# Intervalometer.net
KiCad netlist of a schematic drawn in EAGLE
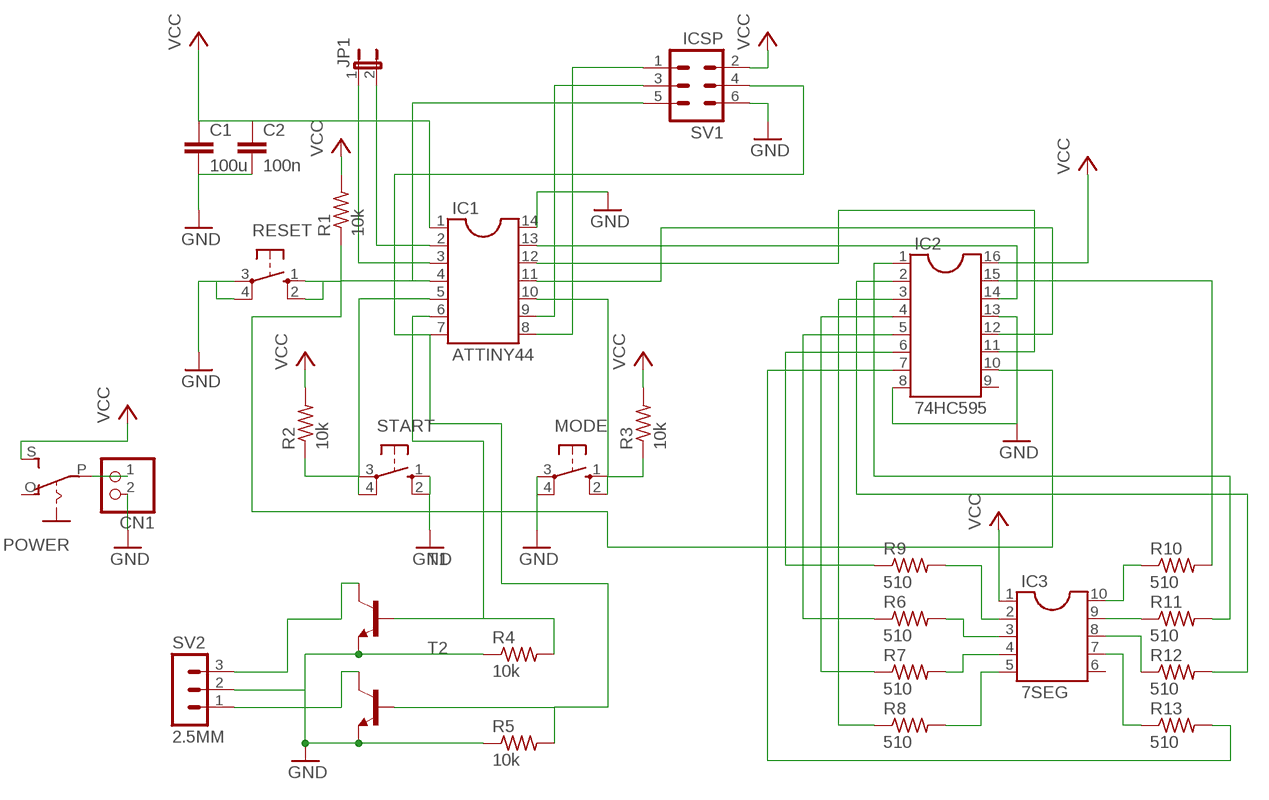
[diagram p0: schematic, sheet 1]

(export (version "E")
  (design (tool "Eeschema 10.0.6"))
  (components
    (comp (ref "C1")
      (value "100u")
      (footprint "eagle-import:C2.5-3")
      (libsource (lib "eagle-import") (part "C2,5-3"))
    )
    (comp (ref "C2")
      (value "100n")
      (footprint "eagle-import:C2.5-3")
      (libsource (lib "eagle-import") (part "C2,5-3"))
    )
    (comp (ref "CN1")
      (value "JST_2PIN-SMT-RA")
      (footprint "eagle-import:JST-PH-2-SMT-RA")
      (libsource (lib "eagle-import") (part "JST_2PIN-SMT-RA"))
    )
    (comp (ref "IC1")
      (value "ATTINY44")
      (footprint "eagle-import:SOCKET-14")
      (libsource (lib "eagle-import") (part "DIL14S"))
    )
    (comp (ref "IC2")
      (value "74HC595")
      (footprint "eagle-import:SOCKET-16")
      (libsource (lib "eagle-import") (part "DIL16S"))
    )
    (comp (ref "IC3")
      (value "7SEG")
      (footprint "eagle-import:DIL10")
      (libsource (lib "eagle-import") (part "DIL10"))
    )
    (comp (ref "JP1")
      (value "JP1E")
      (footprint "eagle-import:JP1")
      (libsource (lib "eagle-import") (part "JP1E"))
    )
    (comp (ref "MODE")
      (value "10-XX")
      (footprint "eagle-import:B3F-10XX")
      (fields (field (name "MPN") "B3F-1000"))
      (libsource (lib "eagle-import") (part "10-XX"))
    )
    (comp (ref "POWER")
      (value "EG1218S")
      (footprint "eagle-import:EG1218")
      (libsource (lib "eagle-import") (part "EG1218S"))
    )
    (comp (ref "R1")
      (value "10k")
      (footprint "eagle-import:0207_10")
      (libsource (lib "eagle-import") (part "R-US_0207/10"))
    )
    (comp (ref "R2")
      (value "10k")
      (footprint "eagle-import:0207_10")
      (libsource (lib "eagle-import") (part "R-US_0207/10"))
    )
    (comp (ref "R3")
      (value "10k")
      (footprint "eagle-import:0207_10")
      (libsource (lib "eagle-import") (part "R-US_0207/10"))
    )
    (comp (ref "R4")
      (value "10k")
      (footprint "eagle-import:0207_10")
      (libsource (lib "eagle-import") (part "R-US_0207/10"))
    )
    (comp (ref "R5")
      (value "10k")
      (footprint "eagle-import:0207_10")
      (libsource (lib "eagle-import") (part "R-US_0207/10"))
    )
    (comp (ref "R6")
      (value "510")
      (footprint "eagle-import:0207_10")
      (libsource (lib "eagle-import") (part "R-US_0207/10"))
    )
    (comp (ref "R7")
      (value "510")
      (footprint "eagle-import:0207_10")
      (libsource (lib "eagle-import") (part "R-US_0207/10"))
    )
    (comp (ref "R8")
      (value "510")
      (footprint "eagle-import:0207_10")
      (libsource (lib "eagle-import") (part "R-US_0207/10"))
    )
    (comp (ref "R9")
      (value "510")
      (footprint "eagle-import:0207_10")
      (libsource (lib "eagle-import") (part "R-US_0207/10"))
    )
    (comp (ref "R10")
      (value "510")
      (footprint "eagle-import:0207_10")
      (libsource (lib "eagle-import") (part "R-US_0207/10"))
    )
    (comp (ref "R11")
      (value "510")
      (footprint "eagle-import:0207_10")
      (libsource (lib "eagle-import") (part "R-US_0207/10"))
    )
    (comp (ref "R12")
      (value "510")
      (footprint "eagle-import:0207_10")
      (libsource (lib "eagle-import") (part "R-US_0207/10"))
    )
    (comp (ref "R13")
      (value "510")
      (footprint "eagle-import:0207_10")
      (libsource (lib "eagle-import") (part "R-US_0207/10"))
    )
    (comp (ref "RESET")
      (value "10-XX")
      (footprint "eagle-import:B3F-10XX")
      (fields (field (name "MPN") "B3F-1000"))
      (libsource (lib "eagle-import") (part "10-XX"))
    )
    (comp (ref "START")
      (value "10-XX")
      (footprint "eagle-import:B3F-10XX")
      (fields (field (name "MPN") "B3F-1000"))
      (libsource (lib "eagle-import") (part "10-XX"))
    )
    (comp (ref "SV1")
      (value "ICSP")
      (footprint "eagle-import:MA03-2")
      (libsource (lib "eagle-import") (part "MA03-2"))
    )
    (comp (ref "SV2")
      (value "2.5MM")
      (footprint "eagle-import:MA03-1")
      (libsource (lib "eagle-import") (part "MA03-1"))
    )
    (comp (ref "T1")
      (value "-NPN-TO92-EBC")
      (footprint "eagle-import:TO92-EBC")
      (libsource (lib "eagle-import") (part "-NPN-TO92-EBC"))
    )
    (comp (ref "T2")
      (value "-NPN-TO92-EBC")
      (footprint "eagle-import:TO92-EBC")
      (libsource (lib "eagle-import") (part "-NPN-TO92-EBC"))
    )
  )
  (nets
    (net (code "1") (name "GND") (class "Default")
      (node (ref "C1") (pin "2") (pinfunction "2_2") (pintype "passive"))
      (node (ref "C2") (pin "2") (pinfunction "2_2") (pintype "passive"))
      (node (ref "CN1") (pin "2") (pinfunction "1_2") (pintype "passive"))
      (node (ref "IC1") (pin "14") (pinfunction "14_14") (pintype "passive"))
      (node (ref "IC2") (pin "13") (pinfunction "13_13") (pintype "passive"))
      (node (ref "IC2") (pin "8") (pinfunction "8_8") (pintype "passive"))
      (node (ref "MODE") (pin "3") (pinfunction "P_3") (pintype "passive"))
      (node (ref "MODE") (pin "4") (pinfunction "P1_4") (pintype "passive"))
      (node (ref "R4") (pin "1") (pinfunction "1_1") (pintype "passive"))
      (node (ref "R5") (pin "1") (pinfunction "1_1") (pintype "passive"))
      (node (ref "RESET") (pin "3") (pinfunction "P_3") (pintype "passive"))
      (node (ref "RESET") (pin "4") (pinfunction "P1_4") (pintype "passive"))
      (node (ref "START") (pin "1") (pinfunction "S_1") (pintype "passive"))
      (node (ref "START") (pin "2") (pinfunction "S1_2") (pintype "passive"))
      (node (ref "SV1") (pin "6") (pinfunction "6_6") (pintype "passive"))
      (node (ref "SV2") (pin "2") (pinfunction "2_2") (pintype "passive"))
      (node (ref "T1") (pin "E") (pinfunction "E_E") (pintype "passive"))
      (node (ref "T2") (pin "E") (pinfunction "E_E") (pintype "passive"))
    )
    (net (code "2") (name "Net-(CN1-2)") (class "Default")
      (node (ref "CN1") (pin "1") (pinfunction "2_1") (pintype "passive"))
      (node (ref "POWER") (pin "P") (pinfunction "P_P") (pintype "passive"))
    )
    (net (code "3") (name "Net-(IC1-Pad2)") (class "Default")
      (node (ref "IC1") (pin "2") (pinfunction "2_2") (pintype "passive"))
      (node (ref "JP1") (pin "2") (pinfunction "2_2") (pintype "passive"))
    )
    (net (code "4") (name "Net-(IC1-Pad3)") (class "Default")
      (node (ref "IC1") (pin "3") (pinfunction "3_3") (pintype "passive"))
      (node (ref "JP1") (pin "1") (pinfunction "1_1") (pintype "passive"))
    )
    (net (code "5") (name "Net-(IC1-Pad6)") (class "Default")
      (node (ref "IC1") (pin "6") (pinfunction "6_6") (pintype "passive"))
      (node (ref "R4") (pin "2") (pinfunction "2_2") (pintype "passive"))
      (node (ref "T1") (pin "B") (pinfunction "B_B") (pintype "passive"))
    )
    (net (code "6") (name "Net-(IC1-Pad7)") (class "Default")
      (node (ref "IC1") (pin "7") (pinfunction "7_7") (pintype "passive"))
      (node (ref "R5") (pin "2") (pinfunction "2_2") (pintype "passive"))
      (node (ref "SV1") (pin "4") (pinfunction "4_4") (pintype "passive"))
      (node (ref "T2") (pin "B") (pinfunction "B_B") (pintype "passive"))
    )
    (net (code "7") (name "Net-(IC1-Pad8)") (class "Default")
      (node (ref "IC1") (pin "8") (pinfunction "8_8") (pintype "passive"))
      (node (ref "SV1") (pin "1") (pinfunction "1_1") (pintype "passive"))
    )
    (net (code "8") (name "Net-(IC1-Pad9)") (class "Default")
      (node (ref "IC1") (pin "9") (pinfunction "9_9") (pintype "passive"))
      (node (ref "SV1") (pin "3") (pinfunction "3_3") (pintype "passive"))
    )
    (net (code "9") (name "Net-(IC1-Pad11)") (class "Default")
      (node (ref "IC1") (pin "11") (pinfunction "11_11") (pintype "passive"))
      (node (ref "IC2") (pin "12") (pinfunction "12_12") (pintype "passive"))
    )
    (net (code "10") (name "Net-(IC1-Pad12)") (class "Default")
      (node (ref "IC1") (pin "12") (pinfunction "12_12") (pintype "passive"))
      (node (ref "IC2") (pin "11") (pinfunction "11_11") (pintype "passive"))
    )
    (net (code "11") (name "Net-(IC1-Pad13)") (class "Default")
      (node (ref "IC1") (pin "13") (pinfunction "13_13") (pintype "passive"))
      (node (ref "IC2") (pin "14") (pinfunction "14_14") (pintype "passive"))
    )
    (net (code "12") (name "Net-(IC2-Pad1)") (class "Default")
      (node (ref "IC2") (pin "1") (pinfunction "1_1") (pintype "passive"))
      (node (ref "R11") (pin "2") (pinfunction "2_2") (pintype "passive"))
    )
    (net (code "13") (name "Net-(IC2-Pad2)") (class "Default")
      (node (ref "IC2") (pin "2") (pinfunction "2_2") (pintype "passive"))
      (node (ref "R12") (pin "2") (pinfunction "2_2") (pintype "passive"))
    )
    (net (code "14") (name "Net-(IC2-Pad3)") (class "Default")
      (node (ref "IC2") (pin "3") (pinfunction "3_3") (pintype "passive"))
      (node (ref "R8") (pin "1") (pinfunction "1_1") (pintype "passive"))
    )
    (net (code "15") (name "Net-(IC2-Pad4)") (class "Default")
      (node (ref "IC2") (pin "4") (pinfunction "4_4") (pintype "passive"))
      (node (ref "R7") (pin "1") (pinfunction "1_1") (pintype "passive"))
    )
    (net (code "16") (name "Net-(IC2-Pad5)") (class "Default")
      (node (ref "IC2") (pin "5") (pinfunction "5_5") (pintype "passive"))
      (node (ref "R6") (pin "1") (pinfunction "1_1") (pintype "passive"))
    )
    (net (code "17") (name "Net-(IC2-Pad6)") (class "Default")
      (node (ref "IC2") (pin "6") (pinfunction "6_6") (pintype "passive"))
      (node (ref "R9") (pin "1") (pinfunction "1_1") (pintype "passive"))
    )
    (net (code "18") (name "Net-(IC2-Pad7)") (class "Default")
      (node (ref "IC2") (pin "7") (pinfunction "7_7") (pintype "passive"))
      (node (ref "R13") (pin "2") (pinfunction "2_2") (pintype "passive"))
    )
    (net (code "19") (name "Net-(IC2-Pad15)") (class "Default")
      (node (ref "IC2") (pin "15") (pinfunction "15_15") (pintype "passive"))
      (node (ref "R10") (pin "2") (pinfunction "2_2") (pintype "passive"))
    )
    (net (code "20") (name "Net-(IC3-Pad2)") (class "Default")
      (node (ref "IC3") (pin "2") (pinfunction "2_2") (pintype "passive"))
      (node (ref "R9") (pin "2") (pinfunction "2_2") (pintype "passive"))
    )
    (net (code "21") (name "Net-(IC3-Pad3)") (class "Default")
      (node (ref "IC3") (pin "3") (pinfunction "3_3") (pintype "passive"))
      (node (ref "R6") (pin "2") (pinfunction "2_2") (pintype "passive"))
    )
    (net (code "22") (name "Net-(IC3-Pad4)") (class "Default")
      (node (ref "IC3") (pin "4") (pinfunction "4_4") (pintype "passive"))
      (node (ref "R7") (pin "2") (pinfunction "2_2") (pintype "passive"))
    )
    (net (code "23") (name "Net-(IC3-Pad5)") (class "Default")
      (node (ref "IC3") (pin "5") (pinfunction "5_5") (pintype "passive"))
      (node (ref "R8") (pin "2") (pinfunction "2_2") (pintype "passive"))
    )
    (net (code "24") (name "Net-(IC3-Pad7)") (class "Default")
      (node (ref "IC3") (pin "7") (pinfunction "7_7") (pintype "passive"))
      (node (ref "R13") (pin "1") (pinfunction "1_1") (pintype "passive"))
    )
    (net (code "25") (name "Net-(IC3-Pad8)") (class "Default")
      (node (ref "IC3") (pin "8") (pinfunction "8_8") (pintype "passive"))
      (node (ref "R12") (pin "1") (pinfunction "1_1") (pintype "passive"))
    )
    (net (code "26") (name "Net-(IC3-Pad9)") (class "Default")
      (node (ref "IC3") (pin "9") (pinfunction "9_9") (pintype "passive"))
      (node (ref "R11") (pin "1") (pinfunction "1_1") (pintype "passive"))
    )
    (net (code "27") (name "Net-(IC3-Pad10)") (class "Default")
      (node (ref "IC3") (pin "10") (pinfunction "10_10") (pintype "passive"))
      (node (ref "R10") (pin "1") (pinfunction "1_1") (pintype "passive"))
    )
    (net (code "28") (name "Net-(MODE-S)") (class "Default")
      (node (ref "IC1") (pin "10") (pinfunction "10_10") (pintype "passive"))
      (node (ref "MODE") (pin "1") (pinfunction "S_1") (pintype "passive"))
      (node (ref "MODE") (pin "2") (pinfunction "S1_2") (pintype "passive"))
      (node (ref "R3") (pin "1") (pinfunction "1_1") (pintype "passive"))
    )
    (net (code "29") (name "Net-(RESET-S)") (class "Default")
      (node (ref "IC1") (pin "4") (pinfunction "4_4") (pintype "passive"))
      (node (ref "IC2") (pin "10") (pinfunction "10_10") (pintype "passive"))
      (node (ref "R1") (pin "1") (pinfunction "1_1") (pintype "passive"))
      (node (ref "RESET") (pin "1") (pinfunction "S_1") (pintype "passive"))
      (node (ref "RESET") (pin "2") (pinfunction "S1_2") (pintype "passive"))
      (node (ref "SV1") (pin "5") (pinfunction "5_5") (pintype "passive"))
    )
    (net (code "30") (name "Net-(START-P)") (class "Default")
      (node (ref "IC1") (pin "5") (pinfunction "5_5") (pintype "passive"))
      (node (ref "R2") (pin "1") (pinfunction "1_1") (pintype "passive"))
      (node (ref "START") (pin "3") (pinfunction "P_3") (pintype "passive"))
      (node (ref "START") (pin "4") (pinfunction "P1_4") (pintype "passive"))
    )
    (net (code "31") (name "Net-(SV2-Pad1)") (class "Default")
      (node (ref "SV2") (pin "1") (pinfunction "1_1") (pintype "passive"))
      (node (ref "T2") (pin "C") (pinfunction "C_C") (pintype "passive"))
    )
    (net (code "32") (name "Net-(SV2-Pad3)") (class "Default")
      (node (ref "SV2") (pin "3") (pinfunction "3_3") (pintype "passive"))
      (node (ref "T1") (pin "C") (pinfunction "C_C") (pintype "passive"))
    )
    (net (code "33") (name "VCC") (class "Default")
      (node (ref "C1") (pin "1") (pinfunction "1_1") (pintype "passive"))
      (node (ref "C2") (pin "1") (pinfunction "1_1") (pintype "passive"))
      (node (ref "IC1") (pin "1") (pinfunction "1_1") (pintype "passive"))
      (node (ref "IC2") (pin "16") (pinfunction "16_16") (pintype "passive"))
      (node (ref "IC3") (pin "1") (pinfunction "1_1") (pintype "passive"))
      (node (ref "POWER") (pin "S") (pinfunction "S_S") (pintype "passive"))
      (node (ref "R1") (pin "2") (pinfunction "2_2") (pintype "passive"))
      (node (ref "R2") (pin "2") (pinfunction "2_2") (pintype "passive"))
      (node (ref "R3") (pin "2") (pinfunction "2_2") (pintype "passive"))
      (node (ref "SV1") (pin "2") (pinfunction "2_2") (pintype "passive"))
    )
    (net (code "34") (name "unconnected-(IC2-Pad9)") (class "Default")
      (node (ref "IC2") (pin "9") (pinfunction "9_9") (pintype "passive"))
    )
    (net (code "35") (name "unconnected-(IC3-Pad6)") (class "Default")
      (node (ref "IC3") (pin "6") (pinfunction "6_6") (pintype "passive"))
    )
    (net (code "36") (name "unconnected-(POWER-PadO)") (class "Default")
      (node (ref "POWER") (pin "O") (pinfunction "O_O") (pintype "passive"))
    )
  )
)
